# ShiftCircuit.net
KiCad netlist of a schematic drawn in EAGLE
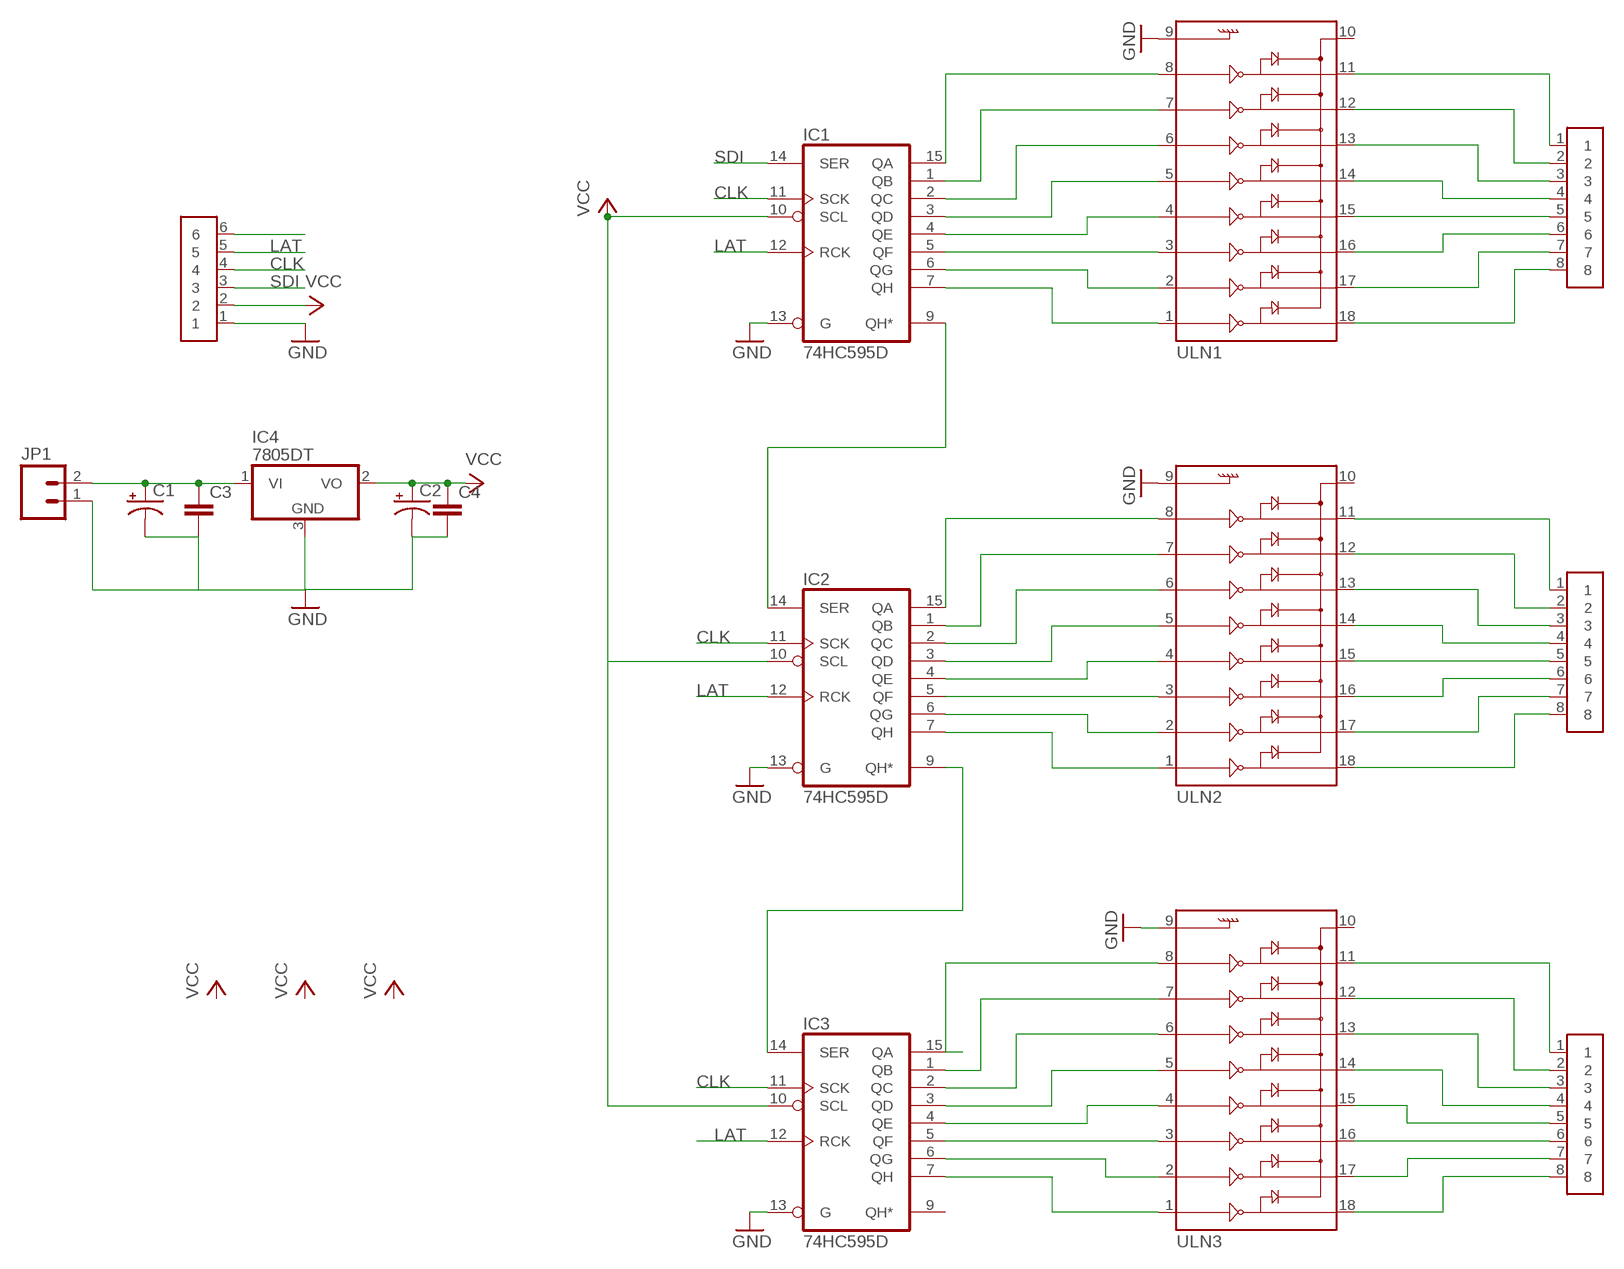
[diagram p0: schematic, sheet 1]

(export (version "E")
  (design (tool "Eeschema 10.0.6"))
  (components
    (comp (ref "C1")
      (value "CAP_POL1206")
      (footprint "eagle-import:EIA3216")
      (libsource (lib "eagle-import") (part "CAP_POL1206"))
    )
    (comp (ref "C2")
      (value "CAP_POL1206")
      (footprint "eagle-import:EIA3216")
      (libsource (lib "eagle-import") (part "CAP_POL1206"))
    )
    (comp (ref "C3")
      (value "C-EUC0805")
      (footprint "eagle-import:C0805")
      (libsource (lib "eagle-import") (part "C-EUC0805"))
    )
    (comp (ref "C4")
      (value "C-EUC0805")
      (footprint "eagle-import:C0805")
      (libsource (lib "eagle-import") (part "C-EUC0805"))
    )
    (comp (ref "IC1")
      (value "74HC595D")
      (footprint "eagle-import:SO16")
      (libsource (lib "eagle-import") (part "74595DHC"))
    )
    (comp (ref "IC2")
      (value "74HC595D")
      (footprint "eagle-import:SO16")
      (libsource (lib "eagle-import") (part "74595DHC"))
    )
    (comp (ref "IC3")
      (value "74HC595D")
      (footprint "eagle-import:SO16")
      (libsource (lib "eagle-import") (part "74595DHC"))
    )
    (comp (ref "IC4")
      (value "7805DT")
      (footprint "eagle-import:TO252")
      (libsource (lib "eagle-import") (part "78DT05"))
    )
    (comp (ref "JP1")
      (value "M02PTH4")
      (footprint "eagle-import:1X02_XTRA_BIG")
      (libsource (lib "eagle-import") (part "M02PTH4"))
    )
    (comp (ref "U$1")
      (value "HEADER8")
      (footprint "eagle-import:HEADER8")
      (libsource (lib "eagle-import") (part "HEADER8"))
    )
    (comp (ref "U$2")
      (value "HEADER8")
      (footprint "eagle-import:HEADER8")
      (libsource (lib "eagle-import") (part "HEADER8"))
    )
    (comp (ref "U$3")
      (value "HEADER8")
      (footprint "eagle-import:HEADER8")
      (libsource (lib "eagle-import") (part "HEADER8"))
    )
    (comp (ref "U$4")
      (value "HEADER6")
      (footprint "eagle-import:HEADER6")
      (libsource (lib "eagle-import") (part "HEADER6"))
    )
    (comp (ref "ULN1")
      (value "ULN2803SOICW")
      (footprint "eagle-import:SO18L")
      (libsource (lib "eagle-import") (part "ULN2803SOICW"))
    )
    (comp (ref "ULN2")
      (value "ULN2803SOICW")
      (footprint "eagle-import:SO18L")
      (libsource (lib "eagle-import") (part "ULN2803SOICW"))
    )
    (comp (ref "ULN3")
      (value "ULN2803SOICW")
      (footprint "eagle-import:SO18L")
      (libsource (lib "eagle-import") (part "ULN2803SOICW"))
    )
  )
  (nets
    (net (code "1") (name "/CLK") (class "Default")
      (node (ref "IC1") (pin "11") (pinfunction "SCK_11") (pintype "input"))
      (node (ref "IC2") (pin "11") (pinfunction "SCK_11") (pintype "input"))
      (node (ref "IC3") (pin "11") (pinfunction "SCK_11") (pintype "input"))
      (node (ref "U$4") (pin "4") (pinfunction "4_4") (pintype "bidirectional"))
    )
    (net (code "2") (name "/LAT") (class "Default")
      (node (ref "IC1") (pin "12") (pinfunction "RCK_12") (pintype "input"))
      (node (ref "IC2") (pin "12") (pinfunction "RCK_12") (pintype "input"))
      (node (ref "IC3") (pin "12") (pinfunction "RCK_12") (pintype "input"))
      (node (ref "U$4") (pin "5") (pinfunction "5_5") (pintype "bidirectional"))
    )
    (net (code "3") (name "/SDI") (class "Default")
      (node (ref "IC1") (pin "14") (pinfunction "SER_14") (pintype "input"))
      (node (ref "U$4") (pin "3") (pinfunction "3_3") (pintype "bidirectional"))
    )
    (net (code "4") (name "GND") (class "Default")
      (node (ref "C1") (pin "C") (pinfunction "-_C") (pintype "passive"))
      (node (ref "C2") (pin "C") (pinfunction "-_C") (pintype "passive"))
      (node (ref "C3") (pin "2") (pinfunction "2_2") (pintype "passive"))
      (node (ref "C4") (pin "2") (pinfunction "2_2") (pintype "passive"))
      (node (ref "IC1") (pin "13") (pinfunction "G_13") (pintype "input"))
      (node (ref "IC2") (pin "13") (pinfunction "G_13") (pintype "input"))
      (node (ref "IC3") (pin "13") (pinfunction "G_13") (pintype "input"))
      (node (ref "IC4") (pin "3") (pinfunction "GND_3") (pintype "passive"))
      (node (ref "JP1") (pin "1") (pinfunction "1_1") (pintype "passive"))
      (node (ref "U$4") (pin "1") (pinfunction "1_1") (pintype "bidirectional"))
      (node (ref "ULN1") (pin "9") (pinfunction "9_9") (pintype "bidirectional"))
      (node (ref "ULN2") (pin "9") (pinfunction "9_9") (pintype "bidirectional"))
      (node (ref "ULN3") (pin "9") (pinfunction "9_9") (pintype "bidirectional"))
    )
    (net (code "5") (name "Net-(C1-+)") (class "Default")
      (node (ref "C1") (pin "A") (pinfunction "+_A") (pintype "passive"))
      (node (ref "C3") (pin "1") (pinfunction "1_1") (pintype "passive"))
      (node (ref "IC4") (pin "1") (pinfunction "VI_1") (pintype "input"))
      (node (ref "JP1") (pin "2") (pinfunction "2_2") (pintype "passive"))
    )
    (net (code "6") (name "Net-(IC1A-QA)") (class "Default")
      (node (ref "IC1") (pin "15") (pinfunction "QA_15") (pintype "tri_state"))
      (node (ref "ULN1") (pin "8") (pinfunction "8_8") (pintype "bidirectional"))
    )
    (net (code "7") (name "Net-(IC1A-QB)") (class "Default")
      (node (ref "IC1") (pin "1") (pinfunction "QB_1") (pintype "tri_state"))
      (node (ref "ULN1") (pin "7") (pinfunction "7_7") (pintype "bidirectional"))
    )
    (net (code "8") (name "Net-(IC1A-QC)") (class "Default")
      (node (ref "IC1") (pin "2") (pinfunction "QC_2") (pintype "tri_state"))
      (node (ref "ULN1") (pin "6") (pinfunction "6_6") (pintype "bidirectional"))
    )
    (net (code "9") (name "Net-(IC1A-QD)") (class "Default")
      (node (ref "IC1") (pin "3") (pinfunction "QD_3") (pintype "tri_state"))
      (node (ref "ULN1") (pin "5") (pinfunction "5_5") (pintype "bidirectional"))
    )
    (net (code "10") (name "Net-(IC1A-QE)") (class "Default")
      (node (ref "IC1") (pin "4") (pinfunction "QE_4") (pintype "tri_state"))
      (node (ref "ULN1") (pin "4") (pinfunction "4_4") (pintype "bidirectional"))
    )
    (net (code "11") (name "Net-(IC1A-QF)") (class "Default")
      (node (ref "IC1") (pin "5") (pinfunction "QF_5") (pintype "tri_state"))
      (node (ref "ULN1") (pin "3") (pinfunction "3_3") (pintype "bidirectional"))
    )
    (net (code "12") (name "Net-(IC1A-QG)") (class "Default")
      (node (ref "IC1") (pin "6") (pinfunction "QG_6") (pintype "tri_state"))
      (node (ref "ULN1") (pin "2") (pinfunction "2_2") (pintype "bidirectional"))
    )
    (net (code "13") (name "Net-(IC1A-QH)") (class "Default")
      (node (ref "IC1") (pin "7") (pinfunction "QH_7") (pintype "tri_state"))
      (node (ref "ULN1") (pin "1") (pinfunction "1_1") (pintype "bidirectional"))
    )
    (net (code "14") (name "Net-(IC1A-QH*)") (class "Default")
      (node (ref "IC1") (pin "9") (pinfunction "QH*_9") (pintype "tri_state"))
      (node (ref "IC2") (pin "14") (pinfunction "SER_14") (pintype "input"))
    )
    (net (code "15") (name "Net-(IC2A-QA)") (class "Default")
      (node (ref "IC2") (pin "15") (pinfunction "QA_15") (pintype "tri_state"))
      (node (ref "ULN2") (pin "8") (pinfunction "8_8") (pintype "bidirectional"))
    )
    (net (code "16") (name "Net-(IC2A-QB)") (class "Default")
      (node (ref "IC2") (pin "1") (pinfunction "QB_1") (pintype "tri_state"))
      (node (ref "ULN2") (pin "7") (pinfunction "7_7") (pintype "bidirectional"))
    )
    (net (code "17") (name "Net-(IC2A-QC)") (class "Default")
      (node (ref "IC2") (pin "2") (pinfunction "QC_2") (pintype "tri_state"))
      (node (ref "ULN2") (pin "6") (pinfunction "6_6") (pintype "bidirectional"))
    )
    (net (code "18") (name "Net-(IC2A-QD)") (class "Default")
      (node (ref "IC2") (pin "3") (pinfunction "QD_3") (pintype "tri_state"))
      (node (ref "ULN2") (pin "5") (pinfunction "5_5") (pintype "bidirectional"))
    )
    (net (code "19") (name "Net-(IC2A-QE)") (class "Default")
      (node (ref "IC2") (pin "4") (pinfunction "QE_4") (pintype "tri_state"))
      (node (ref "ULN2") (pin "4") (pinfunction "4_4") (pintype "bidirectional"))
    )
    (net (code "20") (name "Net-(IC2A-QF)") (class "Default")
      (node (ref "IC2") (pin "5") (pinfunction "QF_5") (pintype "tri_state"))
      (node (ref "ULN2") (pin "3") (pinfunction "3_3") (pintype "bidirectional"))
    )
    (net (code "21") (name "Net-(IC2A-QG)") (class "Default")
      (node (ref "IC2") (pin "6") (pinfunction "QG_6") (pintype "tri_state"))
      (node (ref "ULN2") (pin "2") (pinfunction "2_2") (pintype "bidirectional"))
    )
    (net (code "22") (name "Net-(IC2A-QH)") (class "Default")
      (node (ref "IC2") (pin "7") (pinfunction "QH_7") (pintype "tri_state"))
      (node (ref "ULN2") (pin "1") (pinfunction "1_1") (pintype "bidirectional"))
    )
    (net (code "23") (name "Net-(IC2A-QH*)") (class "Default")
      (node (ref "IC2") (pin "9") (pinfunction "QH*_9") (pintype "tri_state"))
      (node (ref "IC3") (pin "14") (pinfunction "SER_14") (pintype "input"))
    )
    (net (code "24") (name "Net-(IC3A-QA)") (class "Default")
      (node (ref "IC3") (pin "15") (pinfunction "QA_15") (pintype "tri_state"))
      (node (ref "ULN3") (pin "8") (pinfunction "8_8") (pintype "bidirectional"))
    )
    (net (code "25") (name "Net-(IC3A-QB)") (class "Default")
      (node (ref "IC3") (pin "1") (pinfunction "QB_1") (pintype "tri_state"))
      (node (ref "ULN3") (pin "7") (pinfunction "7_7") (pintype "bidirectional"))
    )
    (net (code "26") (name "Net-(IC3A-QC)") (class "Default")
      (node (ref "IC3") (pin "2") (pinfunction "QC_2") (pintype "tri_state"))
      (node (ref "ULN3") (pin "6") (pinfunction "6_6") (pintype "bidirectional"))
    )
    (net (code "27") (name "Net-(IC3A-QD)") (class "Default")
      (node (ref "IC3") (pin "3") (pinfunction "QD_3") (pintype "tri_state"))
      (node (ref "ULN3") (pin "5") (pinfunction "5_5") (pintype "bidirectional"))
    )
    (net (code "28") (name "Net-(IC3A-QE)") (class "Default")
      (node (ref "IC3") (pin "4") (pinfunction "QE_4") (pintype "tri_state"))
      (node (ref "ULN3") (pin "4") (pinfunction "4_4") (pintype "bidirectional"))
    )
    (net (code "29") (name "Net-(IC3A-QF)") (class "Default")
      (node (ref "IC3") (pin "5") (pinfunction "QF_5") (pintype "tri_state"))
      (node (ref "ULN3") (pin "3") (pinfunction "3_3") (pintype "bidirectional"))
    )
    (net (code "30") (name "Net-(IC3A-QG)") (class "Default")
      (node (ref "IC3") (pin "6") (pinfunction "QG_6") (pintype "tri_state"))
      (node (ref "ULN3") (pin "2") (pinfunction "2_2") (pintype "bidirectional"))
    )
    (net (code "31") (name "Net-(IC3A-QH)") (class "Default")
      (node (ref "IC3") (pin "7") (pinfunction "QH_7") (pintype "tri_state"))
      (node (ref "ULN3") (pin "1") (pinfunction "1_1") (pintype "bidirectional"))
    )
    (net (code "32") (name "Net-(U$1-Pad1)") (class "Default")
      (node (ref "U$1") (pin "1") (pinfunction "1_1") (pintype "bidirectional"))
      (node (ref "ULN1") (pin "11") (pinfunction "11_11") (pintype "bidirectional"))
    )
    (net (code "33") (name "Net-(U$1-Pad2)") (class "Default")
      (node (ref "U$1") (pin "2") (pinfunction "2_2") (pintype "bidirectional"))
      (node (ref "ULN1") (pin "12") (pinfunction "12_12") (pintype "bidirectional"))
    )
    (net (code "34") (name "Net-(U$1-Pad3)") (class "Default")
      (node (ref "U$1") (pin "3") (pinfunction "3_3") (pintype "bidirectional"))
      (node (ref "ULN1") (pin "13") (pinfunction "13_13") (pintype "bidirectional"))
    )
    (net (code "35") (name "Net-(U$1-Pad4)") (class "Default")
      (node (ref "U$1") (pin "4") (pinfunction "4_4") (pintype "bidirectional"))
      (node (ref "ULN1") (pin "14") (pinfunction "14_14") (pintype "bidirectional"))
    )
    (net (code "36") (name "Net-(U$1-Pad5)") (class "Default")
      (node (ref "U$1") (pin "5") (pinfunction "5_5") (pintype "bidirectional"))
      (node (ref "ULN1") (pin "15") (pinfunction "15_15") (pintype "bidirectional"))
    )
    (net (code "37") (name "Net-(U$1-Pad6)") (class "Default")
      (node (ref "U$1") (pin "6") (pinfunction "6_6") (pintype "bidirectional"))
      (node (ref "ULN1") (pin "16") (pinfunction "16_16") (pintype "bidirectional"))
    )
    (net (code "38") (name "Net-(U$1-Pad7)") (class "Default")
      (node (ref "U$1") (pin "7") (pinfunction "7_7") (pintype "bidirectional"))
      (node (ref "ULN1") (pin "17") (pinfunction "17_17") (pintype "bidirectional"))
    )
    (net (code "39") (name "Net-(U$1-Pad8)") (class "Default")
      (node (ref "U$1") (pin "8") (pinfunction "8_8") (pintype "bidirectional"))
      (node (ref "ULN1") (pin "18") (pinfunction "18_18") (pintype "bidirectional"))
    )
    (net (code "40") (name "Net-(U$2-Pad1)") (class "Default")
      (node (ref "U$2") (pin "1") (pinfunction "1_1") (pintype "bidirectional"))
      (node (ref "ULN2") (pin "11") (pinfunction "11_11") (pintype "bidirectional"))
    )
    (net (code "41") (name "Net-(U$2-Pad2)") (class "Default")
      (node (ref "U$2") (pin "2") (pinfunction "2_2") (pintype "bidirectional"))
      (node (ref "ULN2") (pin "12") (pinfunction "12_12") (pintype "bidirectional"))
    )
    (net (code "42") (name "Net-(U$2-Pad3)") (class "Default")
      (node (ref "U$2") (pin "3") (pinfunction "3_3") (pintype "bidirectional"))
      (node (ref "ULN2") (pin "13") (pinfunction "13_13") (pintype "bidirectional"))
    )
    (net (code "43") (name "Net-(U$2-Pad4)") (class "Default")
      (node (ref "U$2") (pin "4") (pinfunction "4_4") (pintype "bidirectional"))
      (node (ref "ULN2") (pin "14") (pinfunction "14_14") (pintype "bidirectional"))
    )
    (net (code "44") (name "Net-(U$2-Pad5)") (class "Default")
      (node (ref "U$2") (pin "5") (pinfunction "5_5") (pintype "bidirectional"))
      (node (ref "ULN2") (pin "15") (pinfunction "15_15") (pintype "bidirectional"))
    )
    (net (code "45") (name "Net-(U$2-Pad6)") (class "Default")
      (node (ref "U$2") (pin "6") (pinfunction "6_6") (pintype "bidirectional"))
      (node (ref "ULN2") (pin "16") (pinfunction "16_16") (pintype "bidirectional"))
    )
    (net (code "46") (name "Net-(U$2-Pad7)") (class "Default")
      (node (ref "U$2") (pin "7") (pinfunction "7_7") (pintype "bidirectional"))
      (node (ref "ULN2") (pin "17") (pinfunction "17_17") (pintype "bidirectional"))
    )
    (net (code "47") (name "Net-(U$2-Pad8)") (class "Default")
      (node (ref "U$2") (pin "8") (pinfunction "8_8") (pintype "bidirectional"))
      (node (ref "ULN2") (pin "18") (pinfunction "18_18") (pintype "bidirectional"))
    )
    (net (code "48") (name "Net-(U$3-Pad1)") (class "Default")
      (node (ref "U$3") (pin "1") (pinfunction "1_1") (pintype "bidirectional"))
      (node (ref "ULN3") (pin "11") (pinfunction "11_11") (pintype "bidirectional"))
    )
    (net (code "49") (name "Net-(U$3-Pad2)") (class "Default")
      (node (ref "U$3") (pin "2") (pinfunction "2_2") (pintype "bidirectional"))
      (node (ref "ULN3") (pin "12") (pinfunction "12_12") (pintype "bidirectional"))
    )
    (net (code "50") (name "Net-(U$3-Pad3)") (class "Default")
      (node (ref "U$3") (pin "3") (pinfunction "3_3") (pintype "bidirectional"))
      (node (ref "ULN3") (pin "13") (pinfunction "13_13") (pintype "bidirectional"))
    )
    (net (code "51") (name "Net-(U$3-Pad4)") (class "Default")
      (node (ref "U$3") (pin "4") (pinfunction "4_4") (pintype "bidirectional"))
      (node (ref "ULN3") (pin "14") (pinfunction "14_14") (pintype "bidirectional"))
    )
    (net (code "52") (name "Net-(U$3-Pad5)") (class "Default")
      (node (ref "U$3") (pin "5") (pinfunction "5_5") (pintype "bidirectional"))
      (node (ref "ULN3") (pin "15") (pinfunction "15_15") (pintype "bidirectional"))
    )
    (net (code "53") (name "Net-(U$3-Pad6)") (class "Default")
      (node (ref "U$3") (pin "6") (pinfunction "6_6") (pintype "bidirectional"))
      (node (ref "ULN3") (pin "16") (pinfunction "16_16") (pintype "bidirectional"))
    )
    (net (code "54") (name "Net-(U$3-Pad7)") (class "Default")
      (node (ref "U$3") (pin "7") (pinfunction "7_7") (pintype "bidirectional"))
      (node (ref "ULN3") (pin "17") (pinfunction "17_17") (pintype "bidirectional"))
    )
    (net (code "55") (name "Net-(U$3-Pad8)") (class "Default")
      (node (ref "U$3") (pin "8") (pinfunction "8_8") (pintype "bidirectional"))
      (node (ref "ULN3") (pin "18") (pinfunction "18_18") (pintype "bidirectional"))
    )
    (net (code "56") (name "VCC") (class "Default")
      (node (ref "C2") (pin "A") (pinfunction "+_A") (pintype "passive"))
      (node (ref "C4") (pin "1") (pinfunction "1_1") (pintype "passive"))
      (node (ref "IC1") (pin "10") (pinfunction "SCL_10") (pintype "input"))
      (node (ref "IC2") (pin "10") (pinfunction "SCL_10") (pintype "input"))
      (node (ref "IC3") (pin "10") (pinfunction "SCL_10") (pintype "input"))
      (node (ref "IC4") (pin "2") (pinfunction "VO_2") (pintype "passive"))
      (node (ref "U$4") (pin "2") (pinfunction "2_2") (pintype "bidirectional"))
    )
    (net (code "57") (name "unconnected-(IC3A-QH*-Pad9)") (class "Default")
      (node (ref "IC3") (pin "9") (pinfunction "QH*_9") (pintype "tri_state"))
    )
    (net (code "58") (name "unconnected-(U$4-Pad6)") (class "Default")
      (node (ref "U$4") (pin "6") (pinfunction "6_6") (pintype "bidirectional"))
    )
    (net (code "59") (name "unconnected-(ULN1-Pad10)") (class "Default")
      (node (ref "ULN1") (pin "10") (pinfunction "10_10") (pintype "bidirectional"))
    )
    (net (code "60") (name "unconnected-(ULN2-Pad10)") (class "Default")
      (node (ref "ULN2") (pin "10") (pinfunction "10_10") (pintype "bidirectional"))
    )
    (net (code "61") (name "unconnected-(ULN3-Pad10)") (class "Default")
      (node (ref "ULN3") (pin "10") (pinfunction "10_10") (pintype "bidirectional"))
    )
  )
)
